# LPEM.net
KiCad netlist of a schematic drawn in EAGLE
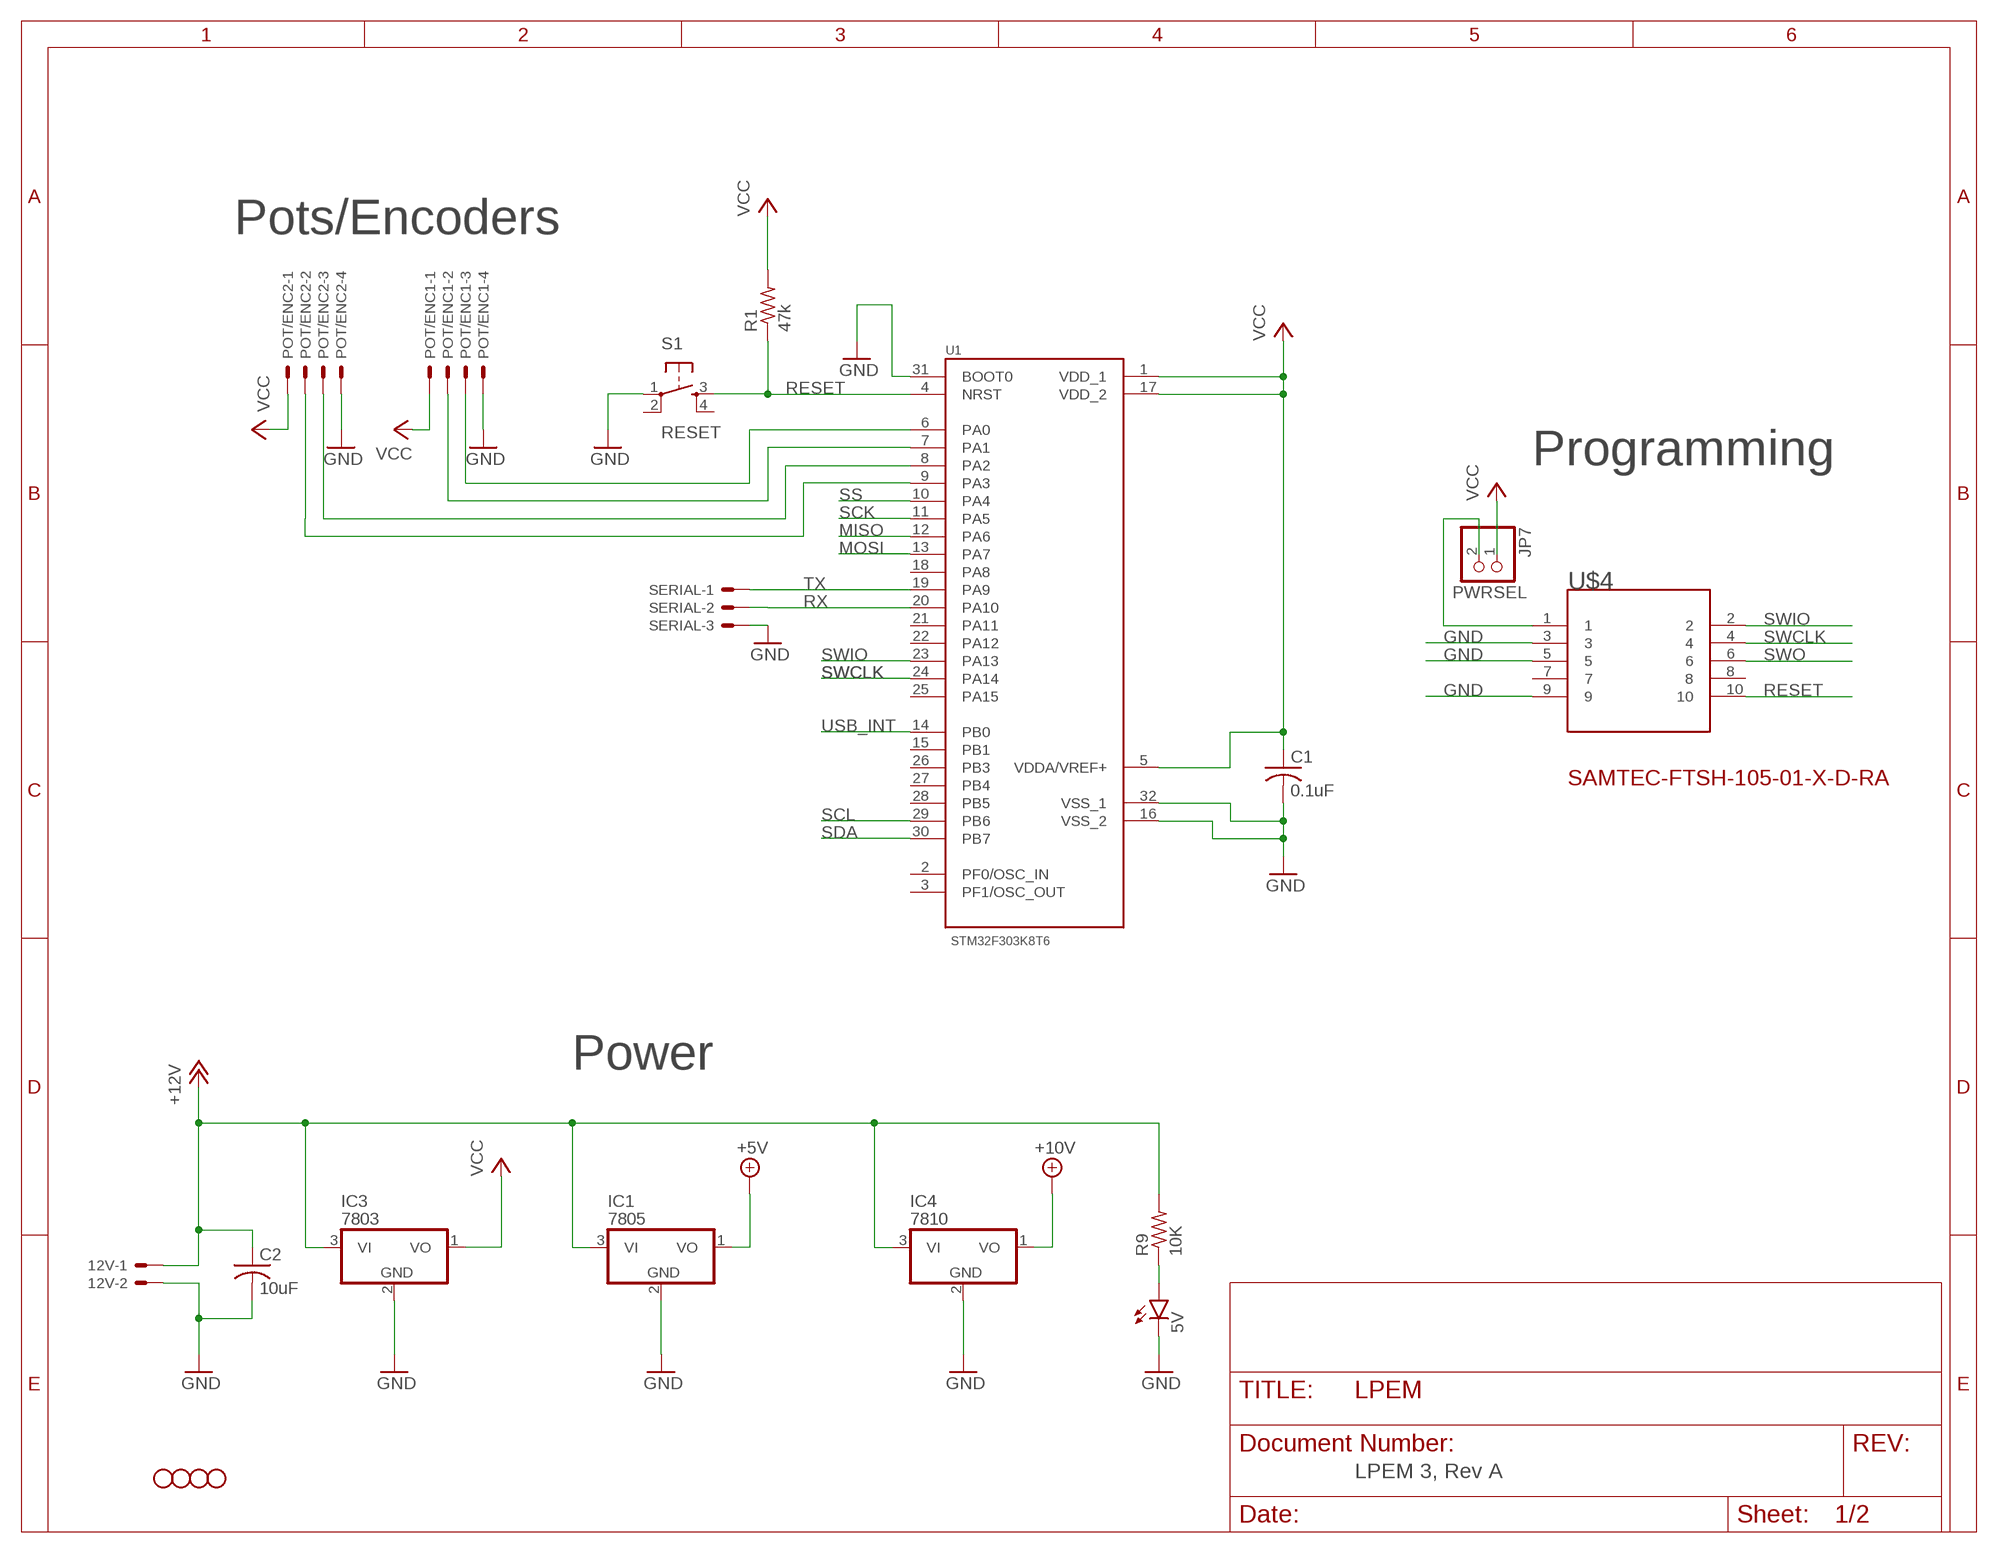
[diagram p0: schematic, sheet 1]
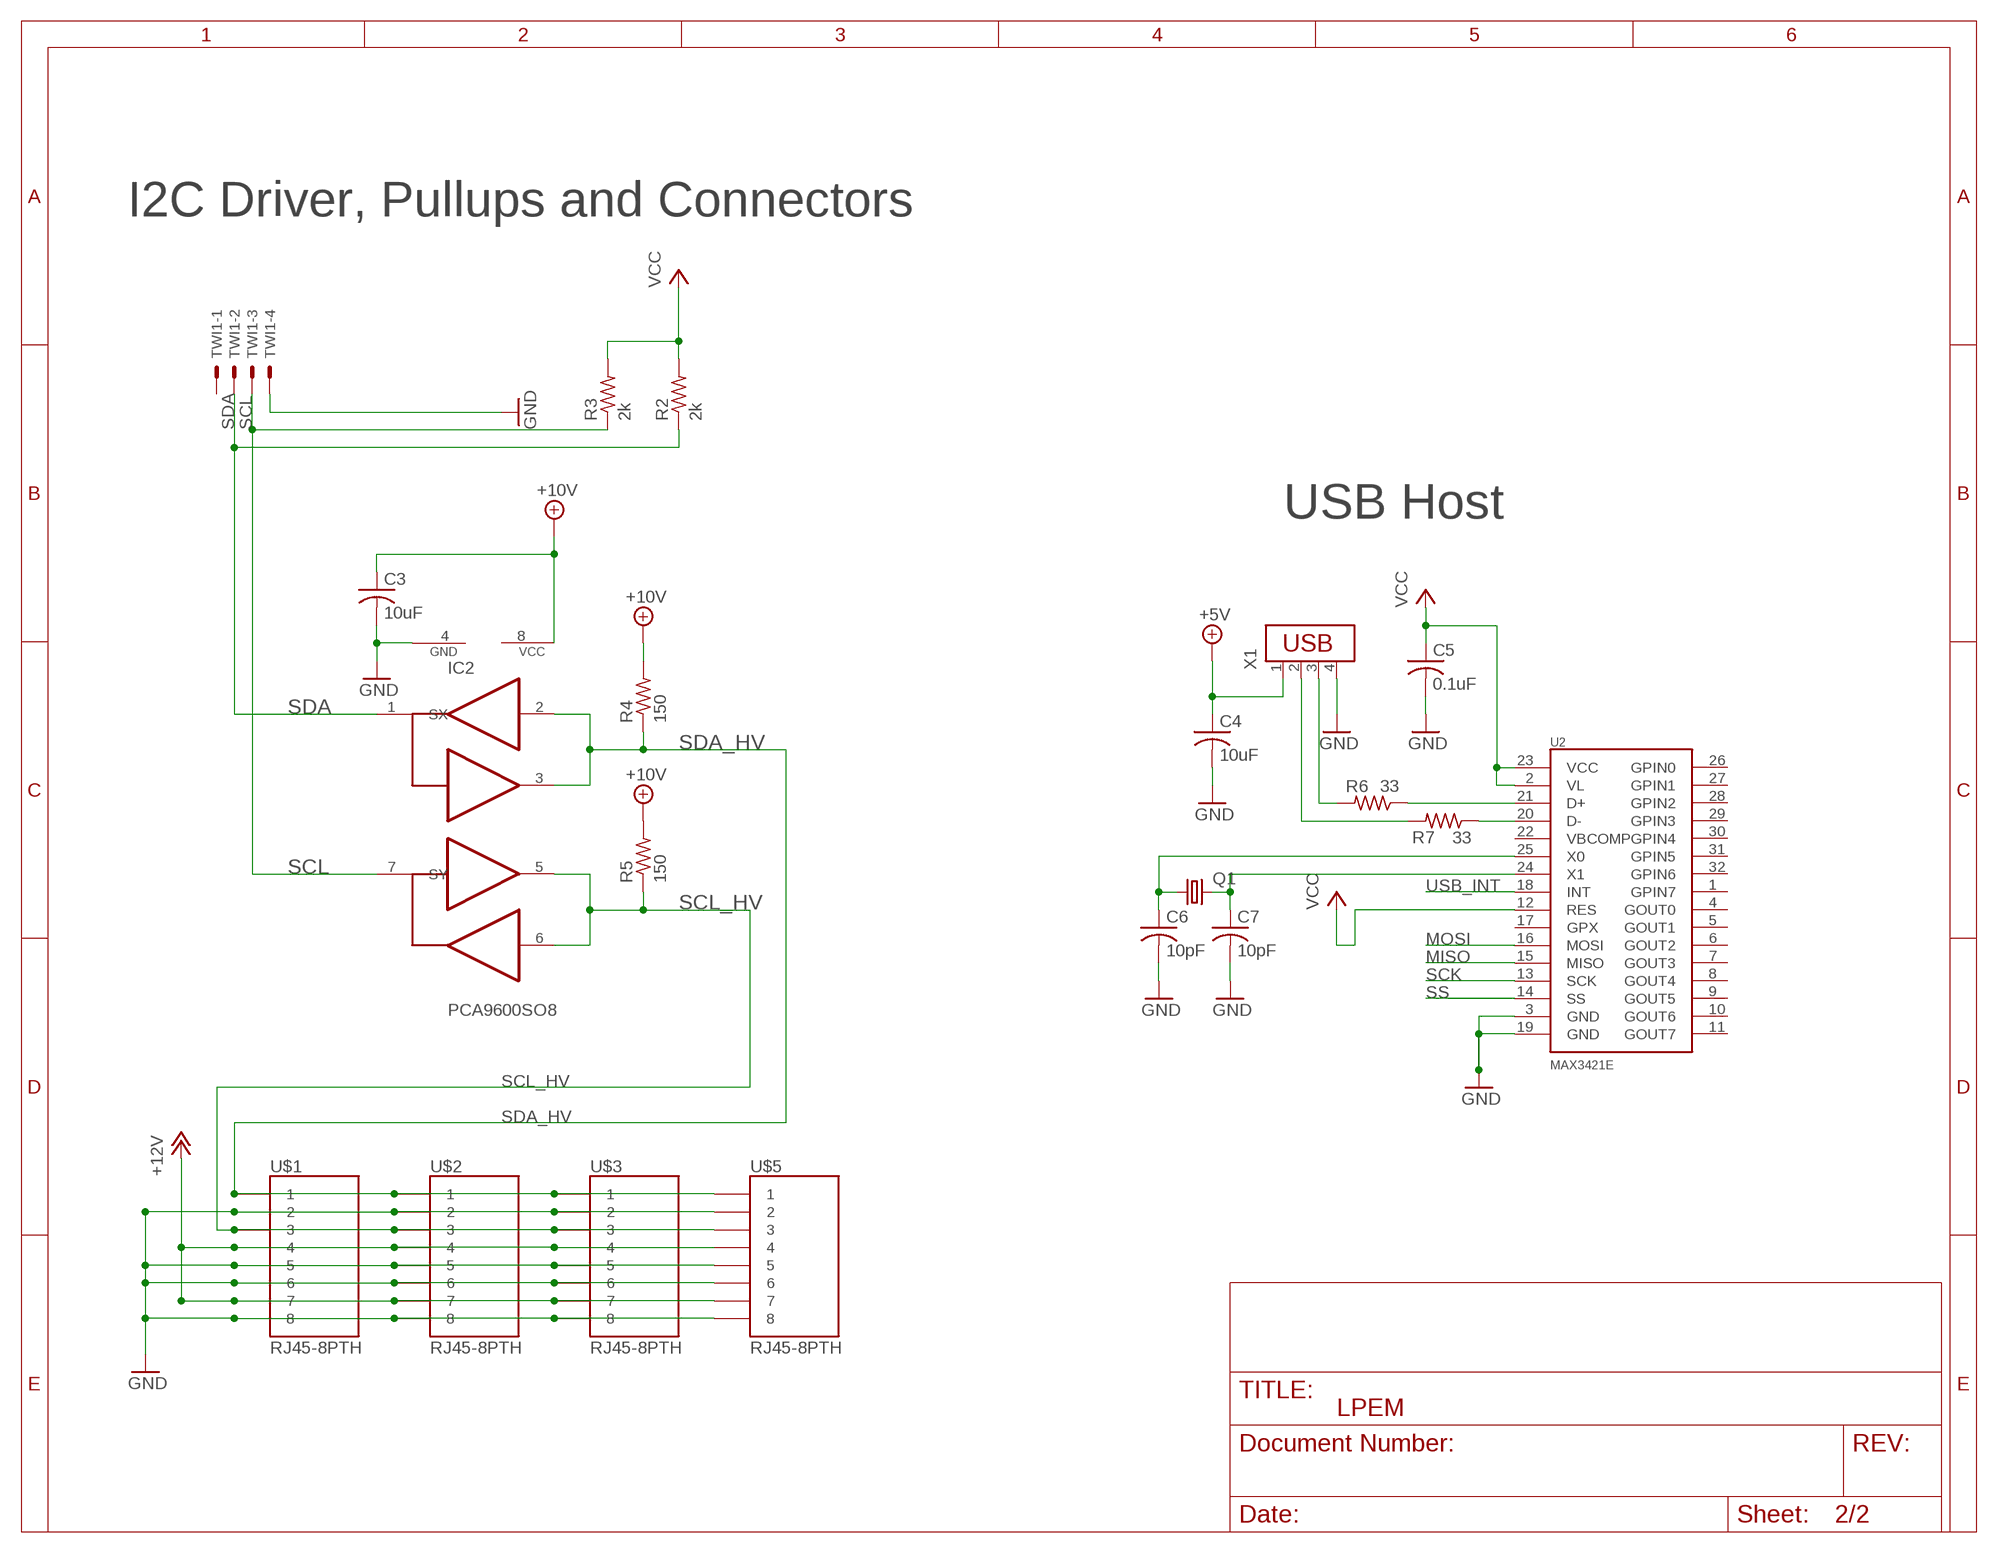
[diagram p1: schematic, sheet 2]

(export (version "E")
  (design (tool "Eeschema 10.0.6"))
  (components
    (comp (ref "5V")
      (value "LED3MM")
      (footprint "eagle-import:LED3MM")
      (libsource (lib "eagle-import") (part "LED3MM"))
    )
    (comp (ref "12V")
      (value "22-23-2021")
      (footprint "eagle-import:22-23-2021")
      (fields (field (name "MF") "MOLEX"))
      (libsource (lib "eagle-import") (part "22-23-2021"))
    )
    (comp (ref "C1")
      (value "0.1uF")
      (footprint "eagle-import:C025-025X050")
      (libsource (lib "eagle-import") (part "C-US025-025X050"))
    )
    (comp (ref "C2")
      (value "10uF")
      (footprint "eagle-import:C025-025X050")
      (libsource (lib "eagle-import") (part "C-US025-025X050"))
    )
    (comp (ref "IC1")
      (value "7805")
      (footprint "eagle-import:TO92")
      (libsource (lib "eagle-import") (part "78ZL05"))
    )
    (comp (ref "IC3")
      (value "7803")
      (footprint "eagle-import:TO92")
      (libsource (lib "eagle-import") (part "78ZL05"))
    )
    (comp (ref "IC4")
      (value "7810")
      (footprint "eagle-import:TO92")
      (libsource (lib "eagle-import") (part "78ZL05"))
    )
    (comp (ref "JP1")
      (value "STAND-OFF")
      (footprint "eagle-import:STAND-OFF")
      (libsource (lib "eagle-import") (part "STAND-OFF"))
    )
    (comp (ref "JP2")
      (value "STAND-OFF")
      (footprint "eagle-import:STAND-OFF")
      (libsource (lib "eagle-import") (part "STAND-OFF"))
    )
    (comp (ref "JP7")
      (value "PWRSEL")
      (footprint "eagle-import:1X02")
      (libsource (lib "eagle-import") (part "PINHD-1X2"))
    )
    (comp (ref "JP8")
      (value "STAND-OFF")
      (footprint "eagle-import:STAND-OFF")
      (libsource (lib "eagle-import") (part "STAND-OFF"))
    )
    (comp (ref "JP9")
      (value "STAND-OFF")
      (footprint "eagle-import:STAND-OFF")
      (libsource (lib "eagle-import") (part "STAND-OFF"))
    )
    (comp (ref "POT/ENC1")
      (value "22-23-2041")
      (footprint "eagle-import:22-23-2041")
      (fields (field (name "MF") "MOLEX"))
      (libsource (lib "eagle-import") (part "22-23-2041"))
    )
    (comp (ref "POT/ENC2")
      (value "22-23-2041")
      (footprint "eagle-import:22-23-2041")
      (fields (field (name "MF") "MOLEX"))
      (libsource (lib "eagle-import") (part "22-23-2041"))
    )
    (comp (ref "R1")
      (value "47k")
      (footprint "eagle-import:0204_5")
      (libsource (lib "eagle-import") (part "R-US_0204/5"))
    )
    (comp (ref "R9")
      (value "10K")
      (footprint "eagle-import:0204_5")
      (libsource (lib "eagle-import") (part "R-US_0204/5"))
    )
    (comp (ref "S1")
      (value "RESET")
      (footprint "eagle-import:TACTILE-PTH")
      (libsource (lib "eagle-import") (part "TAC_SWITCHPTH"))
    )
    (comp (ref "SERIAL")
      (value "22-23-2031")
      (footprint "eagle-import:22-23-2031")
      (fields (field (name "MF") "MOLEX"))
      (libsource (lib "eagle-import") (part "22-23-2031"))
    )
    (comp (ref "U$4")
      (value "SAMTEC-FTSH-105-01-X-D-RAJ")
      (footprint "eagle-import:SAMTEC-FTSH-105-01-X-D-RA")
      (fields (field (name "MF") "Samtec Inc.") (field (name "MP") "FTSH-105-01-L-D-RA-K"))
      (libsource (lib "eagle-import") (part "SAMTEC-FTSH-105-01-X-D-RAJ"))
    )
    (comp (ref "U1")
      (value "STM32F303K8T6")
      (footprint "eagle-import:QFP80P900X900X160-32N")
      (fields (field (name "MF") "STMicroelectronics"))
      (libsource (lib "eagle-import") (part "STM32F303K8T6"))
    )
    (comp (ref "C3")
      (value "10uF")
      (footprint "eagle-import:C025-025X050")
      (libsource (lib "eagle-import") (part "C-US025-025X050"))
    )
    (comp (ref "C4")
      (value "10uF")
      (footprint "eagle-import:C025-025X050")
      (libsource (lib "eagle-import") (part "C-US025-025X050"))
    )
    (comp (ref "C5")
      (value "0.1uF")
      (footprint "eagle-import:C025-025X050")
      (libsource (lib "eagle-import") (part "C-US025-025X050"))
    )
    (comp (ref "C6")
      (value "10pF")
      (footprint "eagle-import:C025-025X050")
      (libsource (lib "eagle-import") (part "C-US025-025X050"))
    )
    (comp (ref "C7")
      (value "10pF")
      (footprint "eagle-import:C025-025X050")
      (libsource (lib "eagle-import") (part "C-US025-025X050"))
    )
    (comp (ref "IC2")
      (value "PCA9600SO8")
      (footprint "eagle-import:SO08")
      (libsource (lib "eagle-import") (part "PCA9600SO8"))
    )
    (comp (ref "Q1")
      (value "CRYSTALHC18U-V")
      (footprint "eagle-import:HC18U-V")
      (libsource (lib "eagle-import") (part "CRYSTALHC18U-V"))
    )
    (comp (ref "R2")
      (value "2k")
      (footprint "eagle-import:0204_5")
      (libsource (lib "eagle-import") (part "R-US_0204/5"))
    )
    (comp (ref "R3")
      (value "2k")
      (footprint "eagle-import:0204_5")
      (libsource (lib "eagle-import") (part "R-US_0204/5"))
    )
    (comp (ref "R4")
      (value "150")
      (footprint "eagle-import:0204_5")
      (libsource (lib "eagle-import") (part "R-US_0204/5"))
    )
    (comp (ref "R5")
      (value "150")
      (footprint "eagle-import:0204_5")
      (libsource (lib "eagle-import") (part "R-US_0204/5"))
    )
    (comp (ref "R6")
      (value "33")
      (footprint "eagle-import:0204_5")
      (libsource (lib "eagle-import") (part "R-US_0204/5"))
    )
    (comp (ref "R7")
      (value "33")
      (footprint "eagle-import:0204_5")
      (libsource (lib "eagle-import") (part "R-US_0204/5"))
    )
    (comp (ref "TWI1")
      (value "22-23-2041")
      (footprint "eagle-import:22-23-2041")
      (fields (field (name "MF") "MOLEX"))
      (libsource (lib "eagle-import") (part "22-23-2041"))
    )
    (comp (ref "U$1")
      (value "RJ45-8PTH")
      (footprint "eagle-import:RJ45-8")
      (libsource (lib "eagle-import") (part "RJ45-8PTH"))
    )
    (comp (ref "U$2")
      (value "RJ45-8PTH")
      (footprint "eagle-import:RJ45-8")
      (libsource (lib "eagle-import") (part "RJ45-8PTH"))
    )
    (comp (ref "U$3")
      (value "RJ45-8PTH")
      (footprint "eagle-import:RJ45-8")
      (libsource (lib "eagle-import") (part "RJ45-8PTH"))
    )
    (comp (ref "U$5")
      (value "RJ45-8PTH")
      (footprint "eagle-import:RJ45-8")
      (libsource (lib "eagle-import") (part "RJ45-8PTH"))
    )
    (comp (ref "U2")
      (value "MAX3421E")
      (footprint "eagle-import:TQFP32-5MM")
      (fields (field (name "MF") "Maxim Integrated"))
      (libsource (lib "eagle-import") (part "MAX3421E"))
    )
    (comp (ref "X1")
      (value "USB-787616")
      (footprint "eagle-import:USB")
      (libsource (lib "eagle-import") (part "USB-787616"))
    )
  )
  (nets
    (net (code "1") (name "+5V") (class "Default")
      (node (ref "C4") (pin "1") (pinfunction "1_1") (pintype "passive"))
      (node (ref "IC1") (pin "1") (pinfunction "VO_1") (pintype "passive"))
      (node (ref "X1") (pin "1") (pinfunction "1_1") (pintype "passive"))
    )
    (net (code "2") (name "+10V") (class "Default")
      (node (ref "C3") (pin "1") (pinfunction "1_1") (pintype "passive"))
      (node (ref "IC2") (pin "8") (pinfunction "VCC_8") (pintype "power_in"))
      (node (ref "IC4") (pin "1") (pinfunction "VO_1") (pintype "passive"))
      (node (ref "R4") (pin "2") (pinfunction "2_2") (pintype "passive"))
      (node (ref "R5") (pin "2") (pinfunction "2_2") (pintype "passive"))
    )
    (net (code "3") (name "+12V") (class "Default")
      (node (ref "12V") (pin "1") (pinfunction "S_1") (pintype "passive"))
      (node (ref "C2") (pin "1") (pinfunction "1_1") (pintype "passive"))
      (node (ref "IC1") (pin "3") (pinfunction "VI_3") (pintype "input"))
      (node (ref "IC3") (pin "3") (pinfunction "VI_3") (pintype "input"))
      (node (ref "IC4") (pin "3") (pinfunction "VI_3") (pintype "input"))
      (node (ref "R9") (pin "2") (pinfunction "2_2") (pintype "passive"))
      (node (ref "U$1") (pin "4") (pinfunction "4_4") (pintype "bidirectional"))
      (node (ref "U$1") (pin "7") (pinfunction "7_7") (pintype "bidirectional"))
      (node (ref "U$2") (pin "4") (pinfunction "4_4") (pintype "bidirectional"))
      (node (ref "U$2") (pin "7") (pinfunction "7_7") (pintype "bidirectional"))
      (node (ref "U$3") (pin "4") (pinfunction "4_4") (pintype "bidirectional"))
      (node (ref "U$3") (pin "7") (pinfunction "7_7") (pintype "bidirectional"))
      (node (ref "U$5") (pin "4") (pinfunction "4_4") (pintype "bidirectional"))
      (node (ref "U$5") (pin "7") (pinfunction "7_7") (pintype "bidirectional"))
    )
    (net (code "4") (name "GND") (class "Default")
      (node (ref "12V") (pin "2") (pinfunction "S_2") (pintype "passive"))
      (node (ref "5V") (pin "K") (pinfunction "C_K") (pintype "passive"))
      (node (ref "C1") (pin "2") (pinfunction "2_2") (pintype "passive"))
      (node (ref "C2") (pin "2") (pinfunction "2_2") (pintype "passive"))
      (node (ref "C3") (pin "2") (pinfunction "2_2") (pintype "passive"))
      (node (ref "C4") (pin "2") (pinfunction "2_2") (pintype "passive"))
      (node (ref "C5") (pin "2") (pinfunction "2_2") (pintype "passive"))
      (node (ref "C6") (pin "2") (pinfunction "2_2") (pintype "passive"))
      (node (ref "C7") (pin "2") (pinfunction "2_2") (pintype "passive"))
      (node (ref "IC1") (pin "2") (pinfunction "GND_2") (pintype "passive"))
      (node (ref "IC2") (pin "4") (pinfunction "GND_4") (pintype "power_in"))
      (node (ref "IC3") (pin "2") (pinfunction "GND_2") (pintype "passive"))
      (node (ref "IC4") (pin "2") (pinfunction "GND_2") (pintype "passive"))
      (node (ref "POT/ENC1") (pin "4") (pinfunction "S_4") (pintype "passive"))
      (node (ref "POT/ENC2") (pin "4") (pinfunction "S_4") (pintype "passive"))
      (node (ref "S1") (pin "1") (pinfunction "1_1") (pintype "passive"))
      (node (ref "SERIAL") (pin "3") (pinfunction "S_3") (pintype "passive"))
      (node (ref "TWI1") (pin "4") (pinfunction "S_4") (pintype "passive"))
      (node (ref "U$1") (pin "2") (pinfunction "2_2") (pintype "bidirectional"))
      (node (ref "U$1") (pin "5") (pinfunction "5_5") (pintype "bidirectional"))
      (node (ref "U$1") (pin "6") (pinfunction "6_6") (pintype "bidirectional"))
      (node (ref "U$1") (pin "8") (pinfunction "8_8") (pintype "bidirectional"))
      (node (ref "U$2") (pin "2") (pinfunction "2_2") (pintype "bidirectional"))
      (node (ref "U$2") (pin "5") (pinfunction "5_5") (pintype "bidirectional"))
      (node (ref "U$2") (pin "6") (pinfunction "6_6") (pintype "bidirectional"))
      (node (ref "U$2") (pin "8") (pinfunction "8_8") (pintype "bidirectional"))
      (node (ref "U$3") (pin "2") (pinfunction "2_2") (pintype "bidirectional"))
      (node (ref "U$3") (pin "5") (pinfunction "5_5") (pintype "bidirectional"))
      (node (ref "U$3") (pin "6") (pinfunction "6_6") (pintype "bidirectional"))
      (node (ref "U$3") (pin "8") (pinfunction "8_8") (pintype "bidirectional"))
      (node (ref "U$4") (pin "3") (pinfunction "3_3") (pintype "passive"))
      (node (ref "U$4") (pin "5") (pinfunction "5_5") (pintype "passive"))
      (node (ref "U$4") (pin "9") (pinfunction "9_9") (pintype "passive"))
      (node (ref "U$5") (pin "2") (pinfunction "2_2") (pintype "bidirectional"))
      (node (ref "U$5") (pin "5") (pinfunction "5_5") (pintype "bidirectional"))
      (node (ref "U$5") (pin "6") (pinfunction "6_6") (pintype "bidirectional"))
      (node (ref "U$5") (pin "8") (pinfunction "8_8") (pintype "bidirectional"))
      (node (ref "U1") (pin "16") (pinfunction "VSS_2_16") (pintype "power_in"))
      (node (ref "U1") (pin "31") (pinfunction "BOOT0_31") (pintype "input"))
      (node (ref "U1") (pin "32") (pinfunction "VSS_1_32") (pintype "power_in"))
      (node (ref "U2") (pin "19") (pinfunction "GND_19") (pintype "bidirectional"))
      (node (ref "U2") (pin "3") (pinfunction "GND_3") (pintype "bidirectional"))
      (node (ref "X1") (pin "4") (pinfunction "4_4") (pintype "passive"))
    )
    (net (code "5") (name "MISO") (class "Default")
      (node (ref "U1") (pin "12") (pinfunction "PA6_12") (pintype "bidirectional"))
      (node (ref "U2") (pin "15") (pinfunction "MISO_15") (pintype "bidirectional"))
    )
    (net (code "6") (name "MOSI") (class "Default")
      (node (ref "U1") (pin "13") (pinfunction "PA7_13") (pintype "bidirectional"))
      (node (ref "U2") (pin "16") (pinfunction "MOSI_16") (pintype "bidirectional"))
    )
    (net (code "7") (name "Net-(5V-PadA)") (class "Default")
      (node (ref "5V") (pin "A") (pinfunction "A_A") (pintype "passive"))
      (node (ref "R9") (pin "1") (pinfunction "1_1") (pintype "passive"))
    )
    (net (code "8") (name "Net-(JP7-Pad2)") (class "Default")
      (node (ref "JP7") (pin "2") (pinfunction "2_2") (pintype "passive"))
      (node (ref "U$4") (pin "1") (pinfunction "1_1") (pintype "passive"))
    )
    (net (code "9") (name "Net-(POT/ENC1B-S)") (class "Default")
      (node (ref "POT/ENC1") (pin "2") (pinfunction "S_2") (pintype "passive"))
      (node (ref "U1") (pin "7") (pinfunction "PA1_7") (pintype "bidirectional"))
    )
    (net (code "10") (name "Net-(POT/ENC1C-S)") (class "Default")
      (node (ref "POT/ENC1") (pin "3") (pinfunction "S_3") (pintype "passive"))
      (node (ref "U1") (pin "6") (pinfunction "PA0_6") (pintype "bidirectional"))
    )
    (net (code "11") (name "Net-(POT/ENC2B-S)") (class "Default")
      (node (ref "POT/ENC2") (pin "2") (pinfunction "S_2") (pintype "passive"))
      (node (ref "U1") (pin "9") (pinfunction "PA3_9") (pintype "bidirectional"))
    )
    (net (code "12") (name "Net-(POT/ENC2C-S)") (class "Default")
      (node (ref "POT/ENC2") (pin "3") (pinfunction "S_3") (pintype "passive"))
      (node (ref "U1") (pin "8") (pinfunction "PA2_8") (pintype "bidirectional"))
    )
    (net (code "13") (name "Net-(R6-Pad2)") (class "Default")
      (node (ref "R6") (pin "2") (pinfunction "2_2") (pintype "passive"))
      (node (ref "X1") (pin "3") (pinfunction "3_3") (pintype "passive"))
    )
    (net (code "14") (name "Net-(R7-Pad2)") (class "Default")
      (node (ref "R7") (pin "2") (pinfunction "2_2") (pintype "passive"))
      (node (ref "X1") (pin "2") (pinfunction "2_2") (pintype "passive"))
    )
    (net (code "15") (name "Net-(U2-D+)") (class "Default")
      (node (ref "R6") (pin "1") (pinfunction "1_1") (pintype "passive"))
      (node (ref "U2") (pin "21") (pinfunction "D+_21") (pintype "bidirectional"))
    )
    (net (code "16") (name "Net-(U2-D-)") (class "Default")
      (node (ref "R7") (pin "1") (pinfunction "1_1") (pintype "passive"))
      (node (ref "U2") (pin "20") (pinfunction "D-_20") (pintype "bidirectional"))
    )
    (net (code "17") (name "Net-(U2-X0)") (class "Default")
      (node (ref "C6") (pin "1") (pinfunction "1_1") (pintype "passive"))
      (node (ref "Q1") (pin "1") (pinfunction "1_1") (pintype "passive"))
      (node (ref "U2") (pin "25") (pinfunction "X0_25") (pintype "bidirectional"))
    )
    (net (code "18") (name "Net-(U2-X1)") (class "Default")
      (node (ref "C7") (pin "1") (pinfunction "1_1") (pintype "passive"))
      (node (ref "Q1") (pin "2") (pinfunction "2_2") (pintype "passive"))
      (node (ref "U2") (pin "24") (pinfunction "X1_24") (pintype "bidirectional"))
    )
    (net (code "19") (name "RESET") (class "Default")
      (node (ref "R1") (pin "1") (pinfunction "1_1") (pintype "passive"))
      (node (ref "S1") (pin "3") (pinfunction "3_3") (pintype "passive"))
      (node (ref "U$4") (pin "10") (pinfunction "10_10") (pintype "passive"))
      (node (ref "U1") (pin "4") (pinfunction "NRST_4") (pintype "bidirectional"))
    )
    (net (code "20") (name "RX") (class "Default")
      (node (ref "SERIAL") (pin "2") (pinfunction "S_2") (pintype "passive"))
      (node (ref "U1") (pin "20") (pinfunction "PA10_20") (pintype "bidirectional"))
    )
    (net (code "21") (name "SCK") (class "Default")
      (node (ref "U1") (pin "11") (pinfunction "PA5_11") (pintype "bidirectional"))
      (node (ref "U2") (pin "13") (pinfunction "SCK_13") (pintype "bidirectional"))
    )
    (net (code "22") (name "SCL") (class "Default")
      (node (ref "IC2") (pin "7") (pinfunction "SY_7") (pintype "bidirectional"))
      (node (ref "R3") (pin "1") (pinfunction "1_1") (pintype "passive"))
      (node (ref "TWI1") (pin "3") (pinfunction "S_3") (pintype "passive"))
      (node (ref "U1") (pin "29") (pinfunction "PB6_29") (pintype "bidirectional"))
    )
    (net (code "23") (name "SCL_HV") (class "Default")
      (node (ref "IC2") (pin "5") (pinfunction "TY_5") (pintype "output"))
      (node (ref "IC2") (pin "6") (pinfunction "RY_6") (pintype "input"))
      (node (ref "R5") (pin "1") (pinfunction "1_1") (pintype "passive"))
      (node (ref "U$1") (pin "3") (pinfunction "3_3") (pintype "bidirectional"))
      (node (ref "U$2") (pin "3") (pinfunction "3_3") (pintype "bidirectional"))
      (node (ref "U$3") (pin "3") (pinfunction "3_3") (pintype "bidirectional"))
      (node (ref "U$5") (pin "3") (pinfunction "3_3") (pintype "bidirectional"))
    )
    (net (code "24") (name "SDA") (class "Default")
      (node (ref "IC2") (pin "1") (pinfunction "SX_1") (pintype "bidirectional"))
      (node (ref "R2") (pin "1") (pinfunction "1_1") (pintype "passive"))
      (node (ref "TWI1") (pin "2") (pinfunction "S_2") (pintype "passive"))
      (node (ref "U1") (pin "30") (pinfunction "PB7_30") (pintype "bidirectional"))
    )
    (net (code "25") (name "SDA_HV") (class "Default")
      (node (ref "IC2") (pin "2") (pinfunction "RX_2") (pintype "input"))
      (node (ref "IC2") (pin "3") (pinfunction "TX_3") (pintype "output"))
      (node (ref "R4") (pin "1") (pinfunction "1_1") (pintype "passive"))
      (node (ref "U$1") (pin "1") (pinfunction "1_1") (pintype "bidirectional"))
      (node (ref "U$2") (pin "1") (pinfunction "1_1") (pintype "bidirectional"))
      (node (ref "U$3") (pin "1") (pinfunction "1_1") (pintype "bidirectional"))
      (node (ref "U$5") (pin "1") (pinfunction "1_1") (pintype "bidirectional"))
    )
    (net (code "26") (name "SS") (class "Default")
      (node (ref "U1") (pin "10") (pinfunction "PA4_10") (pintype "bidirectional"))
      (node (ref "U2") (pin "14") (pinfunction "SS_14") (pintype "bidirectional"))
    )
    (net (code "27") (name "SWCLK") (class "Default")
      (node (ref "U$4") (pin "4") (pinfunction "4_4") (pintype "passive"))
      (node (ref "U1") (pin "24") (pinfunction "PA14_24") (pintype "bidirectional"))
    )
    (net (code "28") (name "SWIO") (class "Default")
      (node (ref "U$4") (pin "2") (pinfunction "2_2") (pintype "passive"))
      (node (ref "U1") (pin "23") (pinfunction "PA13_23") (pintype "bidirectional"))
    )
    (net (code "29") (name "SWO") (class "Default")
      (node (ref "U$4") (pin "6") (pinfunction "6_6") (pintype "passive"))
    )
    (net (code "30") (name "TX") (class "Default")
      (node (ref "SERIAL") (pin "1") (pinfunction "S_1") (pintype "passive"))
      (node (ref "U1") (pin "19") (pinfunction "PA9_19") (pintype "bidirectional"))
    )
    (net (code "31") (name "USB_INT") (class "Default")
      (node (ref "U1") (pin "14") (pinfunction "PB0_14") (pintype "bidirectional"))
      (node (ref "U2") (pin "18") (pinfunction "INT_18") (pintype "bidirectional"))
    )
    (net (code "32") (name "VCC") (class "Default")
      (node (ref "C1") (pin "1") (pinfunction "1_1") (pintype "passive"))
      (node (ref "C5") (pin "1") (pinfunction "1_1") (pintype "passive"))
      (node (ref "IC3") (pin "1") (pinfunction "VO_1") (pintype "passive"))
      (node (ref "JP7") (pin "1") (pinfunction "1_1") (pintype "passive"))
      (node (ref "POT/ENC1") (pin "1") (pinfunction "S_1") (pintype "passive"))
      (node (ref "POT/ENC2") (pin "1") (pinfunction "S_1") (pintype "passive"))
      (node (ref "R1") (pin "2") (pinfunction "2_2") (pintype "passive"))
      (node (ref "R2") (pin "2") (pinfunction "2_2") (pintype "passive"))
      (node (ref "R3") (pin "2") (pinfunction "2_2") (pintype "passive"))
      (node (ref "U1") (pin "1") (pinfunction "VDD_1_1") (pintype "power_in"))
      (node (ref "U1") (pin "17") (pinfunction "VDD_2_17") (pintype "power_in"))
      (node (ref "U1") (pin "5") (pinfunction "VDDA/VREF+_5") (pintype "power_in"))
      (node (ref "U2") (pin "12") (pinfunction "RES_12") (pintype "bidirectional"))
      (node (ref "U2") (pin "2") (pinfunction "VL_2") (pintype "bidirectional"))
      (node (ref "U2") (pin "23") (pinfunction "VCC_23") (pintype "bidirectional"))
    )
    (net (code "33") (name "unconnected-(S1-Pad2)") (class "Default")
      (node (ref "S1") (pin "2") (pinfunction "2_2") (pintype "passive"))
    )
    (net (code "34") (name "unconnected-(S1-Pad4)") (class "Default")
      (node (ref "S1") (pin "4") (pinfunction "4_4") (pintype "passive"))
    )
    (net (code "35") (name "unconnected-(TWI1A-S-Pad1)") (class "Default")
      (node (ref "TWI1") (pin "1") (pinfunction "S_1") (pintype "passive"))
    )
    (net (code "36") (name "unconnected-(U$4-Pad7)") (class "Default")
      (node (ref "U$4") (pin "7") (pinfunction "7_7") (pintype "passive"))
    )
    (net (code "37") (name "unconnected-(U$4-Pad8)") (class "Default")
      (node (ref "U$4") (pin "8") (pinfunction "8_8") (pintype "passive"))
    )
    (net (code "38") (name "unconnected-(U1-PA8-Pad18)") (class "Default")
      (node (ref "U1") (pin "18") (pinfunction "PA8_18") (pintype "bidirectional"))
    )
    (net (code "39") (name "unconnected-(U1-PA11-Pad21)") (class "Default")
      (node (ref "U1") (pin "21") (pinfunction "PA11_21") (pintype "bidirectional"))
    )
    (net (code "40") (name "unconnected-(U1-PA12-Pad22)") (class "Default")
      (node (ref "U1") (pin "22") (pinfunction "PA12_22") (pintype "bidirectional"))
    )
    (net (code "41") (name "unconnected-(U1-PA15-Pad25)") (class "Default")
      (node (ref "U1") (pin "25") (pinfunction "PA15_25") (pintype "bidirectional"))
    )
    (net (code "42") (name "unconnected-(U1-PB1-Pad15)") (class "Default")
      (node (ref "U1") (pin "15") (pinfunction "PB1_15") (pintype "bidirectional"))
    )
    (net (code "43") (name "unconnected-(U1-PB3-Pad26)") (class "Default")
      (node (ref "U1") (pin "26") (pinfunction "PB3_26") (pintype "bidirectional"))
    )
    (net (code "44") (name "unconnected-(U1-PB4-Pad27)") (class "Default")
      (node (ref "U1") (pin "27") (pinfunction "PB4_27") (pintype "bidirectional"))
    )
    (net (code "45") (name "unconnected-(U1-PB5-Pad28)") (class "Default")
      (node (ref "U1") (pin "28") (pinfunction "PB5_28") (pintype "bidirectional"))
    )
    (net (code "46") (name "unconnected-(U1-PF0{slash}OSC_IN-Pad2)") (class "Default")
      (node (ref "U1") (pin "2") (pinfunction "PF0/OSC_IN_2") (pintype "bidirectional"))
    )
    (net (code "47") (name "unconnected-(U1-PF1{slash}OSC_OUT-Pad3)") (class "Default")
      (node (ref "U1") (pin "3") (pinfunction "PF1/OSC_OUT_3") (pintype "bidirectional"))
    )
    (net (code "48") (name "unconnected-(U2-GOUT0-Pad4)") (class "Default")
      (node (ref "U2") (pin "4") (pinfunction "GOUT0_4") (pintype "bidirectional"))
    )
    (net (code "49") (name "unconnected-(U2-GOUT1-Pad5)") (class "Default")
      (node (ref "U2") (pin "5") (pinfunction "GOUT1_5") (pintype "bidirectional"))
    )
    (net (code "50") (name "unconnected-(U2-GOUT2-Pad6)") (class "Default")
      (node (ref "U2") (pin "6") (pinfunction "GOUT2_6") (pintype "bidirectional"))
    )
    (net (code "51") (name "unconnected-(U2-GOUT3-Pad7)") (class "Default")
      (node (ref "U2") (pin "7") (pinfunction "GOUT3_7") (pintype "bidirectional"))
    )
    (net (code "52") (name "unconnected-(U2-GOUT4-Pad8)") (class "Default")
      (node (ref "U2") (pin "8") (pinfunction "GOUT4_8") (pintype "bidirectional"))
    )
    (net (code "53") (name "unconnected-(U2-GOUT5-Pad9)") (class "Default")
      (node (ref "U2") (pin "9") (pinfunction "GOUT5_9") (pintype "bidirectional"))
    )
    (net (code "54") (name "unconnected-(U2-GOUT6-Pad10)") (class "Default")
      (node (ref "U2") (pin "10") (pinfunction "GOUT6_10") (pintype "bidirectional"))
    )
    (net (code "55") (name "unconnected-(U2-GOUT7-Pad11)") (class "Default")
      (node (ref "U2") (pin "11") (pinfunction "GOUT7_11") (pintype "bidirectional"))
    )
    (net (code "56") (name "unconnected-(U2-GPIN0-Pad26)") (class "Default")
      (node (ref "U2") (pin "26") (pinfunction "GPIN0_26") (pintype "bidirectional"))
    )
    (net (code "57") (name "unconnected-(U2-GPIN1-Pad27)") (class "Default")
      (node (ref "U2") (pin "27") (pinfunction "GPIN1_27") (pintype "bidirectional"))
    )
    (net (code "58") (name "unconnected-(U2-GPIN2-Pad28)") (class "Default")
      (node (ref "U2") (pin "28") (pinfunction "GPIN2_28") (pintype "bidirectional"))
    )
    (net (code "59") (name "unconnected-(U2-GPIN3-Pad29)") (class "Default")
      (node (ref "U2") (pin "29") (pinfunction "GPIN3_29") (pintype "bidirectional"))
    )
    (net (code "60") (name "unconnected-(U2-GPIN4-Pad30)") (class "Default")
      (node (ref "U2") (pin "30") (pinfunction "GPIN4_30") (pintype "bidirectional"))
    )
    (net (code "61") (name "unconnected-(U2-GPIN5-Pad31)") (class "Default")
      (node (ref "U2") (pin "31") (pinfunction "GPIN5_31") (pintype "bidirectional"))
    )
    (net (code "62") (name "unconnected-(U2-GPIN6-Pad32)") (class "Default")
      (node (ref "U2") (pin "32") (pinfunction "GPIN6_32") (pintype "bidirectional"))
    )
    (net (code "63") (name "unconnected-(U2-GPIN7-Pad1)") (class "Default")
      (node (ref "U2") (pin "1") (pinfunction "GPIN7_1") (pintype "bidirectional"))
    )
    (net (code "64") (name "unconnected-(U2-GPX-Pad17)") (class "Default")
      (node (ref "U2") (pin "17") (pinfunction "GPX_17") (pintype "bidirectional"))
    )
    (net (code "65") (name "unconnected-(U2-VBCOMP-Pad22)") (class "Default")
      (node (ref "U2") (pin "22") (pinfunction "VBCOMP_22") (pintype "bidirectional"))
    )
  )
)
